# atmega.net
KiCad netlist of a schematic drawn in Altium Designer
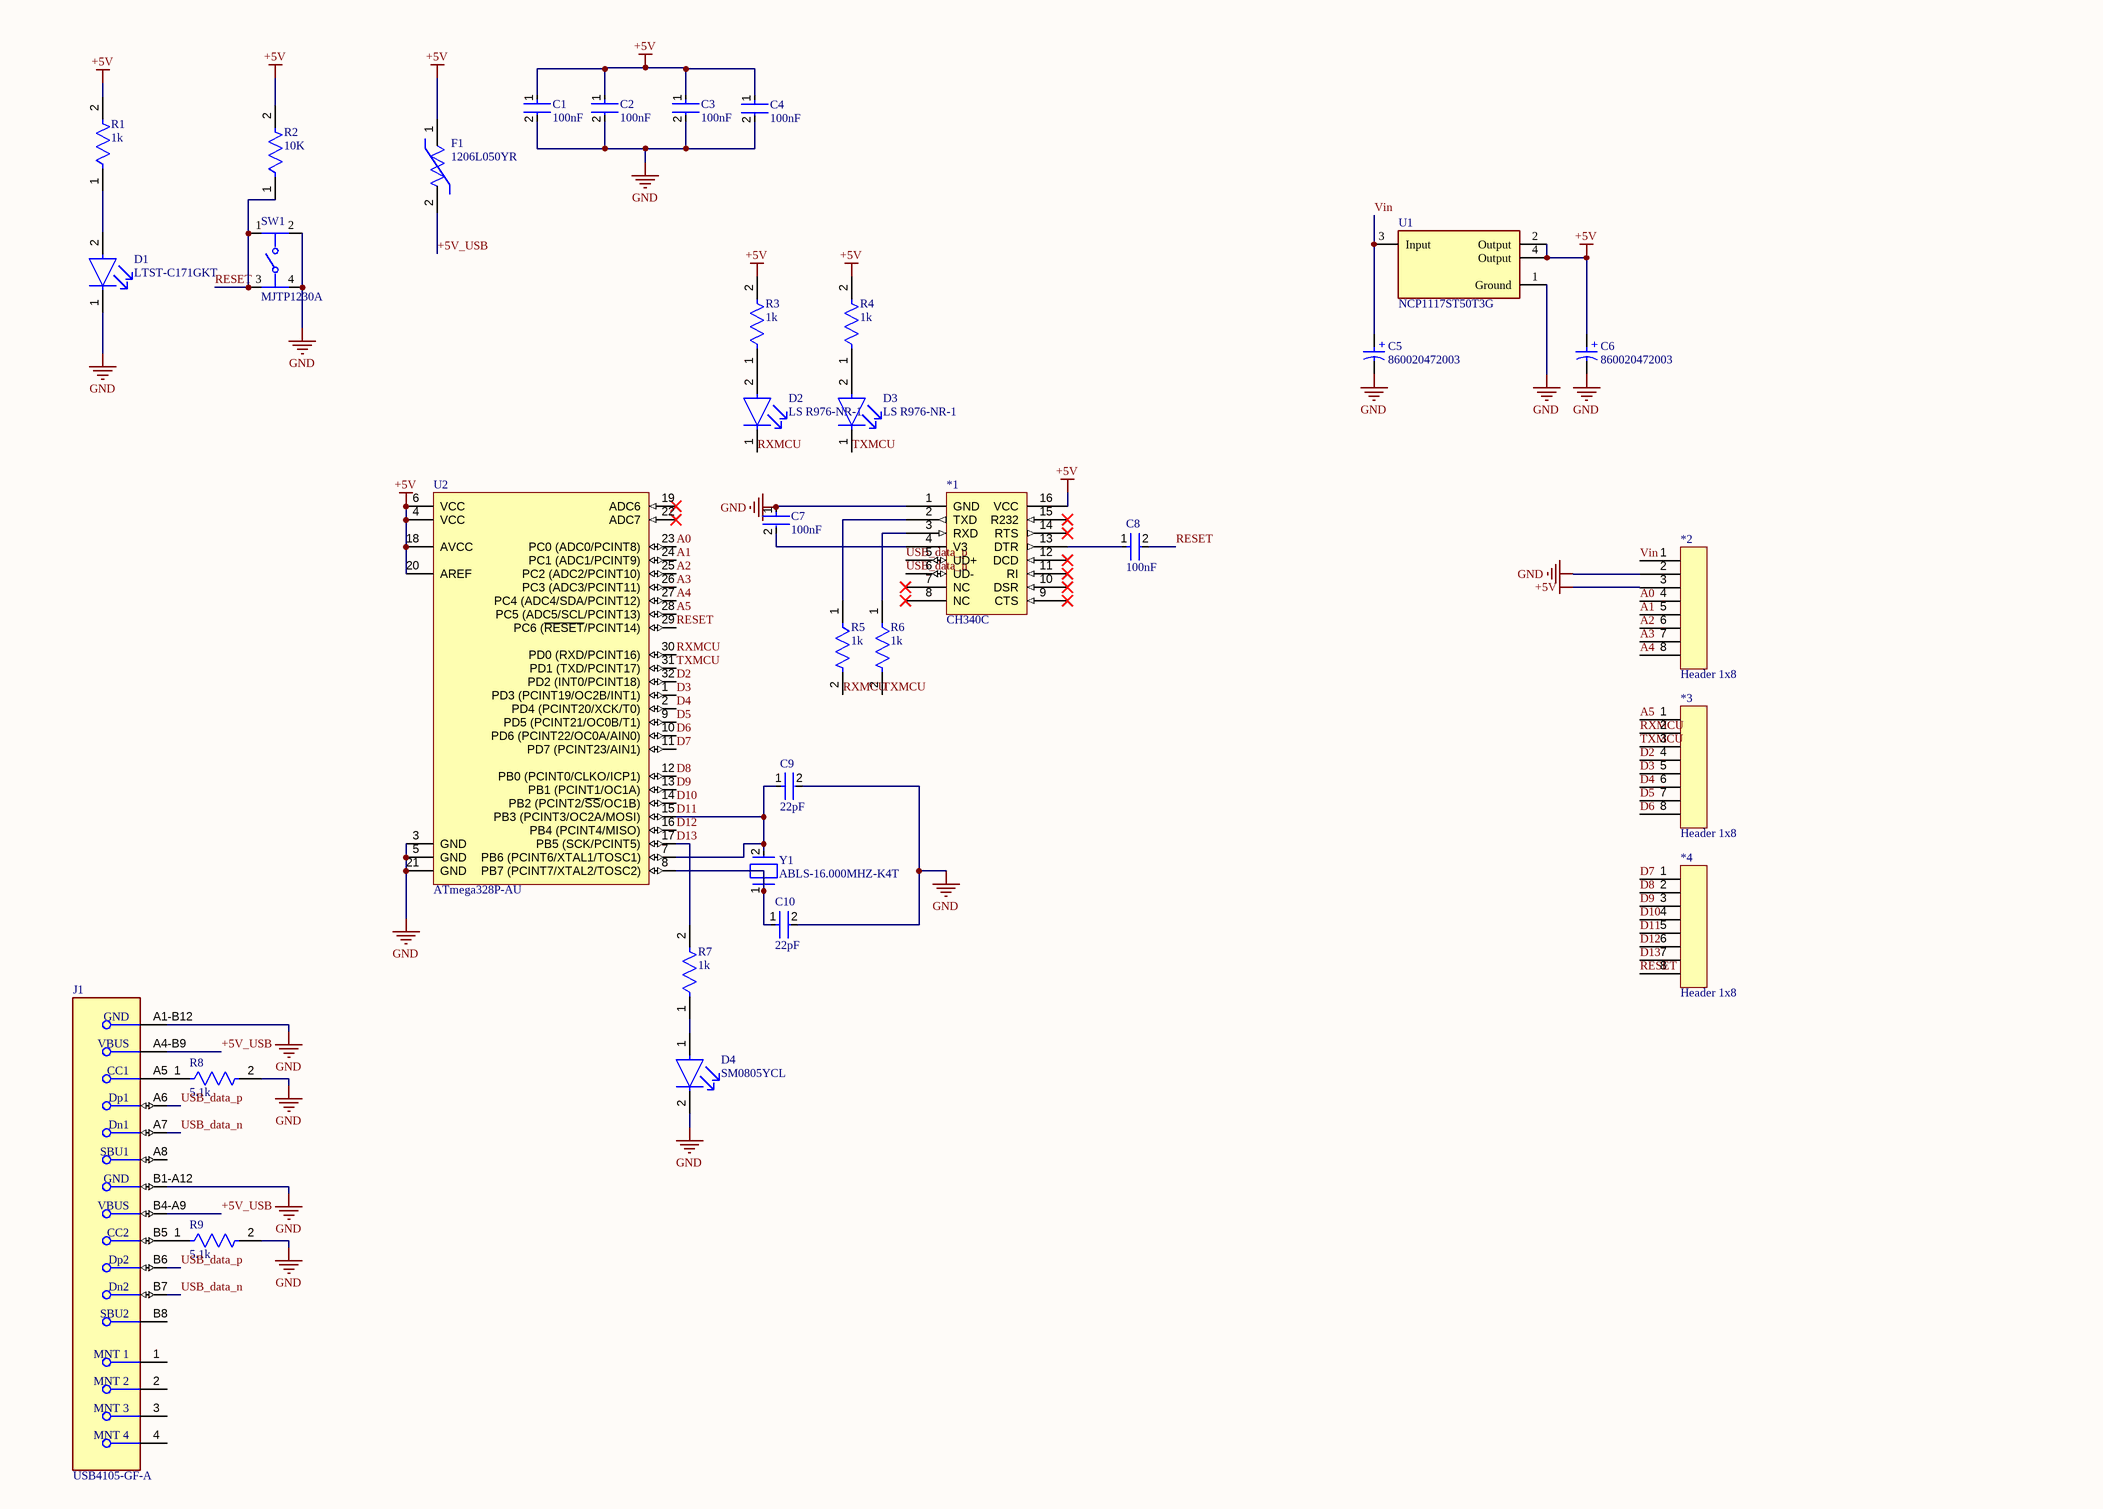
[diagram p0: atmega.SchDoc]

(export (version "E")
  (design (tool "Eeschema 10.0.6"))
  (components
    (comp (ref "*1") (value "CH340C") (footprint "SOP16") (libsource (lib "Schlib1") (part "CH340C")))
    (comp (ref "*2")
      (value "Header 1x8")
      (footprint "Header2.54mm1x8")
      (libsource (lib "Schlib1") (part "Header 1x8"))
    )
    (comp (ref "*3")
      (value "Header 1x8")
      (footprint "Header2.54mm1x8")
      (libsource (lib "Schlib1") (part "Header 1x8"))
    )
    (comp (ref "*4")
      (value "Header 1x8")
      (footprint "Header2.54mm1x8")
      (libsource (lib "Schlib1") (part "Header 1x8"))
    )
    (comp (ref "C1")
      (value "100nF")
      (footprint "FP-CC0805-0_85-MFG")
      (description "CAP CER 0.1UF 50V X7R 0805")
      (fields (field (name "TOLERANCE") "0.1") (field (name "MANUFACTURER PART NUMBER") "CC0805KRX7R9BB104"))
      (libsource (lib "Altium Content Vault") (part "11868f565c42a9108669ba33697ecf6"))
    )
    (comp (ref "C2")
      (value "100nF")
      (footprint "FP-CC0805-0_85-MFG")
      (description "CAP CER 0.1UF 50V X7R 0805")
      (fields (field (name "TOLERANCE") "0.1") (field (name "MANUFACTURER PART NUMBER") "CC0805KRX7R9BB104"))
      (libsource (lib "Altium Content Vault") (part "11868f565c42a9108669ba33697ecf6"))
    )
    (comp (ref "C3")
      (value "100nF")
      (footprint "FP-CC0805-0_85-MFG")
      (description "CAP CER 0.1UF 50V X7R 0805")
      (fields (field (name "TOLERANCE") "0.1") (field (name "MANUFACTURER PART NUMBER") "CC0805KRX7R9BB104"))
      (libsource (lib "Altium Content Vault") (part "11868f565c42a9108669ba33697ecf6"))
    )
    (comp (ref "C4")
      (value "100nF")
      (footprint "FP-CC0805-0_85-MFG")
      (description "CAP CER 0.1UF 50V X7R 0805")
      (fields (field (name "TOLERANCE") "0.1") (field (name "MANUFACTURER PART NUMBER") "CC0805KRX7R9BB104"))
      (libsource (lib "Altium Content Vault") (part "11868f565c42a9108669ba33697ecf6"))
    )
    (comp (ref "C5")
      (value "860020472003")
      (footprint "WCAP-ATG5_D5H11")
      (description "860020472003 WCAP-ATG5 Aluminum Electrolytic Capacitors")
      (fields (field (name "TOLERANCE") "20%"))
      (libsource (lib "Altium Content Vault") (part "Capacitor_Polarized"))
    )
    (comp (ref "C6")
      (value "860020472003")
      (footprint "WCAP-ATG5_D5H11")
      (description "860020472003 WCAP-ATG5 Aluminum Electrolytic Capacitors")
      (fields (field (name "TOLERANCE") "20%"))
      (libsource (lib "Altium Content Vault") (part "Capacitor_Polarized"))
    )
    (comp (ref "C7")
      (value "100nF")
      (footprint "FP-CC0805-0_85-MFG")
      (description "CAP CER 0.1UF 50V X7R 0805")
      (fields (field (name "TOLERANCE") "0.1") (field (name "MANUFACTURER PART NUMBER") "CC0805KRX7R9BB104"))
      (libsource (lib "Altium Content Vault") (part "11868f565c42a9108669ba33697ecf6"))
    )
    (comp (ref "C8")
      (value "100nF")
      (footprint "FP-CC0805-0_85-MFG")
      (description "CAP CER 0.1UF 50V X7R 0805")
      (fields (field (name "TOLERANCE") "0.1") (field (name "MANUFACTURER PART NUMBER") "CC0805KRX7R9BB104"))
      (libsource (lib "Altium Content Vault") (part "11868f565c42a9108669ba33697ecf6"))
    )
    (comp (ref "C9")
      (value "22pF")
      (footprint "FP-C0805C-DN-MFG")
      (description "C0805 22 pF X7R 30ppm/°C 10.00% 50 V")
      (fields (field (name "TOLERANCE") "0.1"))
      (libsource (lib "Altium Content Vault") (part "b4654b650e69147ec39a6b967a45e02"))
    )
    (comp (ref "C10")
      (value "22pF")
      (footprint "FP-C0805C-DN-MFG")
      (description "C0805 22 pF X7R 30ppm/°C 10.00% 50 V")
      (fields (field (name "TOLERANCE") "0.1"))
      (libsource (lib "Altium Content Vault") (part "b4654b650e69147ec39a6b967a45e02"))
    )
    (comp (ref "D1")
      (value "LTST-C171GKT")
      (footprint "FP-LTST-C171GKT-MFG")
      (description "LED GREEN CLEAR CHIP SMD")
      (libsource (lib "Altium Content Vault") (part "8706943c75ba83719d021d2fdc84c58"))
    )
    (comp (ref "D2")
      (value "LS R976-NR-1")
      (footprint "FP-LS_R976-MFG")
      (description "LED RED DIFFUSED 0805 SMD")
      (libsource (lib "Altium Content Vault") (part "8706943c75ba83719d021d2fdc84c58"))
    )
    (comp (ref "D3")
      (value "LS R976-NR-1")
      (footprint "FP-LS_R976-MFG")
      (description "LED RED DIFFUSED 0805 SMD")
      (libsource (lib "Altium Content Vault") (part "8706943c75ba83719d021d2fdc84c58"))
    )
    (comp (ref "D4")
      (value "SM0805YCL")
      (footprint "FP-SM0805YCL-MFG")
      (description "LED YELLOW CLEAR 0805 SMD")
      (libsource (lib "Altium Content Vault") (part "ab1c01a81903e929fc6c44469aada92"))
    )
    (comp (ref "F1")
      (value "1206L050YR")
      (footprint "FP-1206L050YR-MFG")
      (description "PTC RESET FUSE 6V 500MA 1206")
      (libsource (lib "Altium Content Vault") (part "fdf083d5f6389a9a1c4e51137f46658"))
    )
    (comp (ref "J1")
      (value "USB4105-GF-A")
      (footprint "FP-USB4105-GF-A-MFG")
      (description "CONN RCPT USB2.0 TYPEC 5A")
      (fields
        (field (name "MANUFACTURER") "GCT")
        (field (name "OCTOPART") "https://octopart.com/usb4105-gf-a-gct-106627878")
      )
      (libsource (lib "Altium Content Vault") (part "e7c17a616881a82b79941196b4bec10"))
    )
    (comp (ref "R1")
      (value "1k")
      (footprint "FP-RN73R2A-IPC_A")
      (description "1kΩ ±0.1% 0.125W, 1/8W Chip Resistor 0805 (2012 Metric) Moisture Resistant Thin Film")
      (libsource (lib "Altium Content Vault") (part "1029c3af85768c4190bb7ad29bc67b5"))
    )
    (comp (ref "R2")
      (value "10K")
      (footprint "FP-RN73R2A-IPC_A")
      (description "RES 10K OHM 0.1% 1/8W 0805")
      (libsource (lib "Altium Content Vault") (part "1029c3af85768c4190bb7ad29bc67b5"))
    )
    (comp (ref "R3")
      (value "1k")
      (footprint "FP-RN73R2A-IPC_A")
      (description "1kΩ ±0.1% 0.125W, 1/8W Chip Resistor 0805 (2012 Metric) Moisture Resistant Thin Film")
      (libsource (lib "Altium Content Vault") (part "1029c3af85768c4190bb7ad29bc67b5"))
    )
    (comp (ref "R4")
      (value "1k")
      (footprint "FP-RN73R2A-IPC_A")
      (description "1kΩ ±0.1% 0.125W, 1/8W Chip Resistor 0805 (2012 Metric) Moisture Resistant Thin Film")
      (libsource (lib "Altium Content Vault") (part "1029c3af85768c4190bb7ad29bc67b5"))
    )
    (comp (ref "R5")
      (value "1k")
      (footprint "FP-RN73R2A-IPC_A")
      (description "1kΩ ±0.1% 0.125W, 1/8W Chip Resistor 0805 (2012 Metric) Moisture Resistant Thin Film")
      (libsource (lib "Altium Content Vault") (part "1029c3af85768c4190bb7ad29bc67b5"))
    )
    (comp (ref "R6")
      (value "1k")
      (footprint "FP-RN73R2A-IPC_A")
      (description "1kΩ ±0.1% 0.125W, 1/8W Chip Resistor 0805 (2012 Metric) Moisture Resistant Thin Film")
      (libsource (lib "Altium Content Vault") (part "1029c3af85768c4190bb7ad29bc67b5"))
    )
    (comp (ref "R7")
      (value "1k")
      (footprint "FP-RN73R2A-IPC_A")
      (description "1kΩ ±0.1% 0.125W, 1/8W Chip Resistor 0805 (2012 Metric) Moisture Resistant Thin Film")
      (libsource (lib "Altium Content Vault") (part "1029c3af85768c4190bb7ad29bc67b5"))
    )
    (comp (ref "R8")
      (value "5.1k")
      (footprint "FP-MCU0805-IPC_A")
      (description "RES 1.05K OHM 0.5% 1/5W 0805")
      (libsource (lib "Altium Content Vault") (part "1029c3af85768c4190bb7ad29bc67b5"))
    )
    (comp (ref "R9")
      (value "5.1k")
      (footprint "FP-MCU0805-IPC_A")
      (description "RES 1.05K OHM 0.5% 1/5W 0805")
      (libsource (lib "Altium Content Vault") (part "1029c3af85768c4190bb7ad29bc67b5"))
    )
    (comp (ref "SW1")
      (value "MJTP1230A")
      (footprint "FP-MJTP1230A-MFG")
      (description "SWITCH TACTILE SPST-NO 0.05A 12V")
      (libsource (lib "Altium Content Vault") (part "1adf0dd01260c80cf25a44bfd6b99ba"))
    )
    (comp (ref "U1")
      (value "NCP1117ST50T3G")
      (footprint "FP-318H-MFG")
      (description "IC REG LINEAR 5V 1A SOT223")
      (fields (field (name "TOLERANCE") "1%"))
      (libsource (lib "Altium Content Vault") (part "193b6ed835dfa032b90f0234c0cf79c"))
    )
    (comp (ref "U2")
      (value "ATmega328P-AU")
      (footprint "32A_M")
      (libsource (lib "Altium Content Vault") (part "MC-8B-ATM48-SQ32"))
    )
    (comp (ref "Y1")
      (value "ABLS-16.000MHZ-K4T")
      (footprint "FP-ABLS-MFG")
      (description "16MHz ±30ppm Crystal 18pF 40 Ohms HC-49/US")
      (fields (field (name "TOLERANCE") "30ppm"))
      (libsource (lib "Altium Content Vault") (part "c23a69dc6c9e2f18f2079038eb95dd1"))
    )
  )
  (nets
    (net (code "1") (name "+5V") (class "Default")
      (node (ref "*1") (pin "16") (pinfunction "VCC_16") (pintype "power_in"))
      (node (ref "*2") (pin "3") (pintype "passive"))
      (node (ref "C1") (pin "1") (pinfunction "1_1") (pintype "passive"))
      (node (ref "C2") (pin "1") (pinfunction "1_1") (pintype "passive"))
      (node (ref "C3") (pin "1") (pinfunction "1_1") (pintype "passive"))
      (node (ref "C4") (pin "1") (pinfunction "1_1") (pintype "passive"))
      (node (ref "C6") (pin "1") (pinfunction "P_1") (pintype "passive"))
      (node (ref "F1") (pin "1") (pinfunction "1_1") (pintype "passive"))
      (node (ref "R1") (pin "2") (pinfunction "2_2") (pintype "passive"))
      (node (ref "R2") (pin "2") (pinfunction "2_2") (pintype "passive"))
      (node (ref "R3") (pin "2") (pinfunction "2_2") (pintype "passive"))
      (node (ref "R4") (pin "2") (pinfunction "2_2") (pintype "passive"))
      (node (ref "U1") (pin "2") (pinfunction "Output_2") (pintype "power_in"))
      (node (ref "U1") (pin "4") (pinfunction "Output_4") (pintype "power_in"))
      (node (ref "U2") (pin "18") (pinfunction "AVCC_18") (pintype "power_in"))
      (node (ref "U2") (pin "20") (pinfunction "AREF_20") (pintype "passive"))
      (node (ref "U2") (pin "4") (pinfunction "VCC_4") (pintype "power_in"))
      (node (ref "U2") (pin "6") (pinfunction "VCC_6") (pintype "power_in"))
    )
    (net (code "2") (name "/+5V_USB") (class "Default")
      (node (ref "F1") (pin "2") (pinfunction "2_2") (pintype "passive"))
      (node (ref "J1") (pin "A4-B9") (pinfunction "VBUS_A4-B9") (pintype "power_in"))
      (node (ref "J1") (pin "B4-A9") (pinfunction "VBUS_B4-A9") (pintype "bidirectional"))
    )
    (net (code "3") (name "/A0") (class "Default")
      (node (ref "*2") (pin "4") (pintype "passive"))
      (node (ref "U2") (pin "23") (pinfunction "PC0_(ADC0/PCINT8)_23") (pintype "bidirectional"))
    )
    (net (code "4") (name "/A1") (class "Default")
      (node (ref "*2") (pin "5") (pintype "passive"))
      (node (ref "U2") (pin "24") (pinfunction "PC1_(ADC1/PCINT9)_24") (pintype "bidirectional"))
    )
    (net (code "5") (name "/A2") (class "Default")
      (node (ref "*2") (pin "6") (pintype "passive"))
      (node (ref "U2") (pin "25") (pinfunction "PC2_(ADC2/PCINT10)_25") (pintype "bidirectional"))
    )
    (net (code "6") (name "/A3") (class "Default")
      (node (ref "*2") (pin "7") (pintype "passive"))
      (node (ref "U2") (pin "26") (pinfunction "PC3_(ADC3/PCINT11)_26") (pintype "bidirectional"))
    )
    (net (code "7") (name "/A4") (class "Default")
      (node (ref "*2") (pin "8") (pintype "passive"))
      (node (ref "U2") (pin "27") (pinfunction "PC4_(ADC4/SDA/PCINT12)_27") (pintype "bidirectional"))
    )
    (net (code "8") (name "/A5") (class "Default")
      (node (ref "*3") (pin "1") (pintype "passive"))
      (node (ref "U2") (pin "28") (pinfunction "PC5_(ADC5/SCL/PCINT13)_28") (pintype "bidirectional"))
    )
    (net (code "9") (name "/D2") (class "Default")
      (node (ref "*3") (pin "4") (pintype "passive"))
      (node (ref "U2") (pin "32") (pinfunction "PD2_(INT0/PCINT18)_32") (pintype "bidirectional"))
    )
    (net (code "10") (name "/D3") (class "Default")
      (node (ref "*3") (pin "5") (pintype "passive"))
      (node (ref "U2") (pin "1") (pinfunction "PD3_(PCINT19/OC2B/INT1)_1") (pintype "bidirectional"))
    )
    (net (code "11") (name "/D4") (class "Default")
      (node (ref "*3") (pin "6") (pintype "passive"))
      (node (ref "U2") (pin "2") (pinfunction "PD4_(PCINT20/XCK/T0)_2") (pintype "bidirectional"))
    )
    (net (code "12") (name "/D5") (class "Default")
      (node (ref "*3") (pin "7") (pintype "passive"))
      (node (ref "U2") (pin "9") (pinfunction "PD5_(PCINT21/OC0B/T1)_9") (pintype "bidirectional"))
    )
    (net (code "13") (name "/D6") (class "Default")
      (node (ref "*3") (pin "8") (pintype "passive"))
      (node (ref "U2") (pin "10") (pinfunction "PD6_(PCINT22/OC0A/AIN0)_10") (pintype "bidirectional"))
    )
    (net (code "14") (name "/D7") (class "Default")
      (node (ref "*4") (pin "1") (pintype "passive"))
      (node (ref "U2") (pin "11") (pinfunction "PD7_(PCINT23/AIN1)_11") (pintype "bidirectional"))
    )
    (net (code "15") (name "/D8") (class "Default")
      (node (ref "*4") (pin "2") (pintype "passive"))
      (node (ref "U2") (pin "12") (pinfunction "PB0_(PCINT0/CLKO/ICP1)_12") (pintype "bidirectional"))
    )
    (net (code "16") (name "/D9") (class "Default")
      (node (ref "*4") (pin "3") (pintype "passive"))
      (node (ref "U2") (pin "13") (pinfunction "PB1_(PCINT1/OC1A)_13") (pintype "bidirectional"))
    )
    (net (code "17") (name "/D10") (class "Default")
      (node (ref "*4") (pin "4") (pintype "passive"))
      (node (ref "U2") (pin "14") (pinfunction "PB2_(PCINT2/~{SS}/OC1B)_14") (pintype "bidirectional"))
    )
    (net (code "18") (name "/D11") (class "Default")
      (node (ref "*4") (pin "5") (pintype "passive"))
      (node (ref "C9") (pin "1") (pinfunction "1_1") (pintype "passive"))
      (node (ref "U2") (pin "15") (pinfunction "PB3_(PCINT3/OC2A/MOSI)_15") (pintype "bidirectional"))
      (node (ref "U2") (pin "7") (pinfunction "PB6_(PCINT6/XTAL1/TOSC1)_7") (pintype "bidirectional"))
      (node (ref "Y1") (pin "2") (pinfunction "2_2") (pintype "passive"))
    )
    (net (code "19") (name "/D12") (class "Default")
      (node (ref "*4") (pin "6") (pintype "passive"))
      (node (ref "U2") (pin "16") (pinfunction "PB4_(PCINT4/MISO)_16") (pintype "bidirectional"))
    )
    (net (code "20") (name "/D13") (class "Default")
      (node (ref "*4") (pin "7") (pintype "passive"))
      (node (ref "R7") (pin "2") (pinfunction "2_2") (pintype "passive"))
      (node (ref "U2") (pin "17") (pinfunction "PB5_(SCK/PCINT5)_17") (pintype "bidirectional"))
    )
    (net (code "21") (name "/RESET") (class "Default")
      (node (ref "*4") (pin "8") (pintype "passive"))
      (node (ref "C8") (pin "2") (pinfunction "2_2") (pintype "passive"))
      (node (ref "R2") (pin "1") (pinfunction "1_1") (pintype "passive"))
      (node (ref "SW1") (pin "1") (pinfunction "1_1") (pintype "passive"))
      (node (ref "SW1") (pin "3") (pinfunction "3_3") (pintype "passive"))
      (node (ref "U2") (pin "29") (pinfunction "PC6_(~{RESET}/PCINT14)_29") (pintype "bidirectional"))
    )
    (net (code "22") (name "/RXMCU") (class "Default")
      (node (ref "*3") (pin "2") (pintype "passive"))
      (node (ref "D2") (pin "1") (pinfunction "C_1") (pintype "passive"))
      (node (ref "R5") (pin "2") (pinfunction "2_2") (pintype "passive"))
      (node (ref "U2") (pin "30") (pinfunction "PD0_(RXD/PCINT16)_30") (pintype "bidirectional"))
    )
    (net (code "23") (name "/TXMCU") (class "Default")
      (node (ref "*3") (pin "3") (pintype "passive"))
      (node (ref "D3") (pin "1") (pinfunction "C_1") (pintype "passive"))
      (node (ref "R6") (pin "2") (pinfunction "2_2") (pintype "passive"))
      (node (ref "U2") (pin "31") (pinfunction "PD1_(TXD/PCINT17)_31") (pintype "bidirectional"))
    )
    (net (code "24") (name "/USB_data_n") (class "Default")
      (node (ref "*1") (pin "6") (pinfunction "UD-_6") (pintype "bidirectional"))
      (node (ref "J1") (pin "A7") (pinfunction "Dn1_A7") (pintype "bidirectional"))
      (node (ref "J1") (pin "B7") (pinfunction "Dn2_B7") (pintype "bidirectional"))
    )
    (net (code "25") (name "/USB_data_p") (class "Default")
      (node (ref "*1") (pin "5") (pinfunction "UD+_5") (pintype "bidirectional"))
      (node (ref "J1") (pin "A6") (pinfunction "Dp1_A6") (pintype "bidirectional"))
      (node (ref "J1") (pin "B6") (pinfunction "Dp2_B6") (pintype "bidirectional"))
    )
    (net (code "26") (name "/Vin") (class "Default")
      (node (ref "*2") (pin "1") (pintype "passive"))
      (node (ref "C5") (pin "1") (pinfunction "P_1") (pintype "passive"))
      (node (ref "U1") (pin "3") (pinfunction "Input_3") (pintype "power_in"))
    )
    (net (code "27") (name "GND") (class "Default")
      (node (ref "*1") (pin "1") (pinfunction "GND_1") (pintype "power_in"))
      (node (ref "*2") (pin "2") (pintype "passive"))
      (node (ref "C1") (pin "2") (pinfunction "2_2") (pintype "passive"))
      (node (ref "C10") (pin "2") (pinfunction "2_2") (pintype "passive"))
      (node (ref "C2") (pin "2") (pinfunction "2_2") (pintype "passive"))
      (node (ref "C3") (pin "2") (pinfunction "2_2") (pintype "passive"))
      (node (ref "C4") (pin "2") (pinfunction "2_2") (pintype "passive"))
      (node (ref "C5") (pin "2") (pinfunction "N_2") (pintype "passive"))
      (node (ref "C6") (pin "2") (pinfunction "N_2") (pintype "passive"))
      (node (ref "C7") (pin "1") (pinfunction "1_1") (pintype "passive"))
      (node (ref "C9") (pin "2") (pinfunction "2_2") (pintype "passive"))
      (node (ref "D1") (pin "1") (pinfunction "C_1") (pintype "passive"))
      (node (ref "D4") (pin "2") (pinfunction "C_2") (pintype "passive"))
      (node (ref "J1") (pin "A1-B12") (pinfunction "GND_A1-B12") (pintype "power_in"))
      (node (ref "J1") (pin "B1-A12") (pinfunction "GND_B1-A12") (pintype "bidirectional"))
      (node (ref "R8") (pin "2") (pinfunction "2_2") (pintype "passive"))
      (node (ref "R9") (pin "2") (pinfunction "2_2") (pintype "passive"))
      (node (ref "SW1") (pin "2") (pinfunction "2_2") (pintype "passive"))
      (node (ref "SW1") (pin "4") (pinfunction "4_4") (pintype "passive"))
      (node (ref "U1") (pin "1") (pinfunction "Ground_1") (pintype "power_in"))
      (node (ref "U2") (pin "21") (pinfunction "GND_21") (pintype "power_in"))
      (node (ref "U2") (pin "3") (pinfunction "GND_3") (pintype "power_in"))
      (node (ref "U2") (pin "5") (pinfunction "GND_5") (pintype "power_in"))
    )
    (net (code "28") (name "Net-(*1-DTR)") (class "Default")
      (node (ref "*1") (pin "13") (pinfunction "DTR_13") (pintype "output"))
      (node (ref "C8") (pin "1") (pinfunction "1_1") (pintype "passive"))
    )
    (net (code "29") (name "Net-(*1-RXD)") (class "Default")
      (node (ref "*1") (pin "3") (pinfunction "RXD_3") (pintype "input"))
      (node (ref "R6") (pin "1") (pinfunction "1_1") (pintype "passive"))
    )
    (net (code "30") (name "Net-(*1-TXD)") (class "Default")
      (node (ref "*1") (pin "2") (pinfunction "TXD_2") (pintype "output"))
      (node (ref "R5") (pin "1") (pinfunction "1_1") (pintype "passive"))
    )
    (net (code "31") (name "Net-(*1-V3)") (class "Default")
      (node (ref "*1") (pin "4") (pinfunction "V3_4") (pintype "passive"))
      (node (ref "C7") (pin "2") (pinfunction "2_2") (pintype "passive"))
    )
    (net (code "32") (name "Net-(D1-A)") (class "Default")
      (node (ref "D1") (pin "2") (pinfunction "A_2") (pintype "passive"))
      (node (ref "R1") (pin "1") (pinfunction "1_1") (pintype "passive"))
    )
    (net (code "33") (name "Net-(D2-A)") (class "Default")
      (node (ref "D2") (pin "2") (pinfunction "A_2") (pintype "passive"))
      (node (ref "R3") (pin "1") (pinfunction "1_1") (pintype "passive"))
    )
    (net (code "34") (name "Net-(D3-A)") (class "Default")
      (node (ref "D3") (pin "2") (pinfunction "A_2") (pintype "passive"))
      (node (ref "R4") (pin "1") (pinfunction "1_1") (pintype "passive"))
    )
    (net (code "35") (name "Net-(D4-A)") (class "Default")
      (node (ref "D4") (pin "1") (pinfunction "A_1") (pintype "passive"))
      (node (ref "R7") (pin "1") (pinfunction "1_1") (pintype "passive"))
    )
    (net (code "36") (name "Net-(J1-CC1)") (class "Default")
      (node (ref "J1") (pin "A5") (pinfunction "CC1_A5") (pintype "power_in"))
      (node (ref "R8") (pin "1") (pinfunction "1_1") (pintype "passive"))
    )
    (net (code "37") (name "Net-(J1-CC2)") (class "Default")
      (node (ref "J1") (pin "B5") (pinfunction "CC2_B5") (pintype "bidirectional"))
      (node (ref "R9") (pin "1") (pinfunction "1_1") (pintype "passive"))
    )
    (net (code "38") (name "Net-(U2-PB7_(PCINT7{slash}XTAL2{slash}TOSC2))") (class "Default")
      (node (ref "C10") (pin "1") (pinfunction "1_1") (pintype "passive"))
      (node (ref "U2") (pin "8") (pinfunction "PB7_(PCINT7/XTAL2/TOSC2)_8") (pintype "bidirectional"))
      (node (ref "Y1") (pin "1") (pinfunction "1_1") (pintype "passive"))
    )
    (net (code "39") (name "unconnected-(*1-CTS-Pad9)") (class "Default")
      (node (ref "*1") (pin "9") (pinfunction "CTS_9") (pintype "input+no_connect"))
    )
    (net (code "40") (name "unconnected-(*1-DCD-Pad12)") (class "Default")
      (node (ref "*1") (pin "12") (pinfunction "DCD_12") (pintype "input+no_connect"))
    )
    (net (code "41") (name "unconnected-(*1-DSR-Pad10)") (class "Default")
      (node (ref "*1") (pin "10") (pinfunction "DSR_10") (pintype "input+no_connect"))
    )
    (net (code "42") (name "unconnected-(*1-NC-Pad7)") (class "Default")
      (node (ref "*1") (pin "7") (pinfunction "NC_7") (pintype "passive+no_connect"))
    )
    (net (code "43") (name "unconnected-(*1-NC-Pad8)") (class "Default")
      (node (ref "*1") (pin "8") (pinfunction "NC_8") (pintype "passive+no_connect"))
    )
    (net (code "44") (name "unconnected-(*1-R232-Pad15)") (class "Default")
      (node (ref "*1") (pin "15") (pinfunction "R232_15") (pintype "input+no_connect"))
    )
    (net (code "45") (name "unconnected-(*1-RI-Pad11)") (class "Default")
      (node (ref "*1") (pin "11") (pinfunction "RI_11") (pintype "input+no_connect"))
    )
    (net (code "46") (name "unconnected-(*1-RTS-Pad14)") (class "Default")
      (node (ref "*1") (pin "14") (pinfunction "RTS_14") (pintype "output+no_connect"))
    )
    (net (code "47") (name "unconnected-(J1-MNT_1-Pad1)") (class "Default")
      (node (ref "J1") (pin "1") (pinfunction "MNT_1_1") (pintype "power_in"))
    )
    (net (code "48") (name "unconnected-(J1-MNT_2-Pad2)") (class "Default")
      (node (ref "J1") (pin "2") (pinfunction "MNT_2_2") (pintype "power_in"))
    )
    (net (code "49") (name "unconnected-(J1-MNT_3-Pad3)") (class "Default")
      (node (ref "J1") (pin "3") (pinfunction "MNT_3_3") (pintype "power_in"))
    )
    (net (code "50") (name "unconnected-(J1-MNT_4-Pad4)") (class "Default")
      (node (ref "J1") (pin "4") (pinfunction "MNT_4_4") (pintype "power_in"))
    )
    (net (code "51") (name "unconnected-(J1-SBU1-PadA8)") (class "Default")
      (node (ref "J1") (pin "A8") (pinfunction "SBU1_A8") (pintype "bidirectional"))
    )
    (net (code "52") (name "unconnected-(J1-SBU2-PadB8)") (class "Default")
      (node (ref "J1") (pin "B8") (pinfunction "SBU2_B8") (pintype "power_in"))
    )
    (net (code "53") (name "unconnected-(U2-ADC6-Pad19)") (class "Default")
      (node (ref "U2") (pin "19") (pinfunction "ADC6_19") (pintype "input+no_connect"))
    )
    (net (code "54") (name "unconnected-(U2-ADC7-Pad22)") (class "Default")
      (node (ref "U2") (pin "22") (pinfunction "ADC7_22") (pintype "input+no_connect"))
    )
  )
)
